# PS.net
KiCad netlist of a schematic drawn in Altium Designer
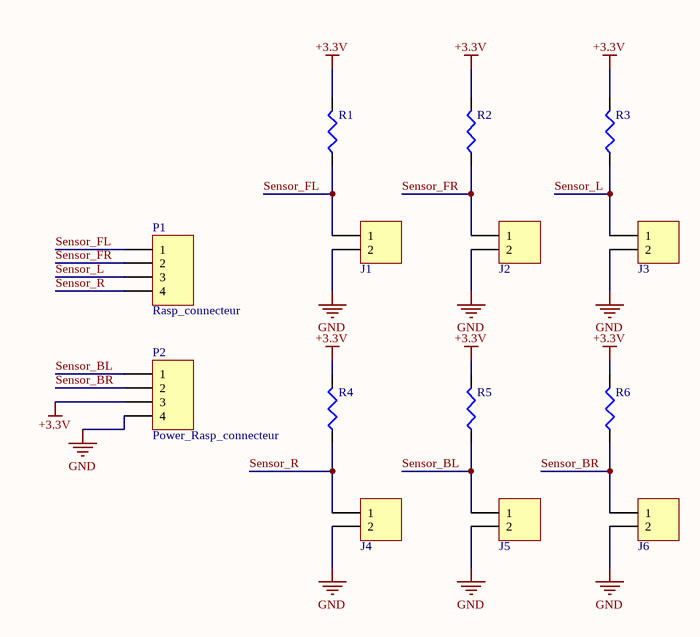
[diagram p0: PS.SchDoc]

(export (version "E")
  (design (tool "Eeschema 10.0.6"))
  (components
    (comp (ref "J1")
      (value "Connecteur 2")
      (footprint "Header_2Ecam")
      (description "Connecteur")
      (fields (field (name "DESIGNER") "ECAM 2005"))
      (libsource (lib "HBLib") (part "Connecteur 2"))
    )
    (comp (ref "J2")
      (value "Connecteur 2")
      (footprint "Header_2Ecam")
      (description "Connecteur")
      (fields (field (name "DESIGNER") "ECAM 2005"))
      (libsource (lib "HBLib") (part "Connecteur 2"))
    )
    (comp (ref "J3")
      (value "Connecteur 2")
      (footprint "Header_2Ecam")
      (description "Connecteur")
      (fields (field (name "DESIGNER") "ECAM 2005"))
      (libsource (lib "HBLib") (part "Connecteur 2"))
    )
    (comp (ref "J4")
      (value "Connecteur 2")
      (footprint "Header_2Ecam")
      (description "Connecteur")
      (fields (field (name "DESIGNER") "ECAM 2005"))
      (libsource (lib "HBLib") (part "Connecteur 2"))
    )
    (comp (ref "J5")
      (value "Connecteur 2")
      (footprint "Header_2Ecam")
      (description "Connecteur")
      (fields (field (name "DESIGNER") "ECAM 2005"))
      (libsource (lib "HBLib") (part "Connecteur 2"))
    )
    (comp (ref "J6")
      (value "Connecteur 2")
      (footprint "Header_2Ecam")
      (description "Connecteur")
      (fields (field (name "DESIGNER") "ECAM 2005"))
      (libsource (lib "HBLib") (part "Connecteur 2"))
    )
    (comp (ref "P1")
      (value "Rasp_connecteur")
      (footprint "Header4_ecam")
      (description "Header, 4-Pin")
      (fields (field (name "PUBLISHER") "Altium Limited"))
      (libsource (lib "HBLib") (part "Header 4"))
    )
    (comp (ref "P2")
      (value "Power_Rasp_connecteur")
      (footprint "Header4_ecam")
      (description "Header, 4-Pin")
      (fields (field (name "PUBLISHER") "Altium Limited"))
      (libsource (lib "HBLib") (part "Header 4"))
    )
    (comp (ref "R1")
      (value "Résistance")
      (footprint "AXIAL-0.3")
      (description "Résistance standard")
      (fields (field (name "DESIGNER") "ECAM 2005"))
      (libsource (lib "ECAM") (part "Résistance"))
    )
    (comp (ref "R2")
      (value "Résistance")
      (footprint "AXIAL-0.3")
      (description "Résistance standard")
      (fields (field (name "DESIGNER") "ECAM 2005"))
      (libsource (lib "ECAM") (part "Résistance"))
    )
    (comp (ref "R3")
      (value "Résistance")
      (footprint "AXIAL-0.3")
      (description "Résistance standard")
      (fields (field (name "DESIGNER") "ECAM 2005"))
      (libsource (lib "ECAM") (part "Résistance"))
    )
    (comp (ref "R4")
      (value "Résistance")
      (footprint "AXIAL-0.3")
      (description "Résistance standard")
      (fields (field (name "DESIGNER") "ECAM 2005"))
      (libsource (lib "ECAM") (part "Résistance"))
    )
    (comp (ref "R5")
      (value "Résistance")
      (footprint "AXIAL-0.3")
      (description "Résistance standard")
      (fields (field (name "DESIGNER") "ECAM 2005"))
      (libsource (lib "ECAM") (part "Résistance"))
    )
    (comp (ref "R6")
      (value "Résistance")
      (footprint "AXIAL-0.3")
      (description "Résistance standard")
      (fields (field (name "DESIGNER") "ECAM 2005"))
      (libsource (lib "ECAM") (part "Résistance"))
    )
  )
  (nets
    (net (code "1") (name "+3.3V") (class "Default")
      (node (ref "P2") (pin "3") (pinfunction "3_3") (pintype "passive"))
      (node (ref "R1") (pin "2") (pinfunction "2_2") (pintype "passive"))
      (node (ref "R2") (pin "2") (pinfunction "2_2") (pintype "passive"))
      (node (ref "R3") (pin "2") (pinfunction "2_2") (pintype "passive"))
      (node (ref "R4") (pin "2") (pinfunction "2_2") (pintype "passive"))
      (node (ref "R5") (pin "2") (pinfunction "2_2") (pintype "passive"))
      (node (ref "R6") (pin "2") (pinfunction "2_2") (pintype "passive"))
    )
    (net (code "2") (name "/Sensor_BL") (class "Default")
      (node (ref "J5") (pin "1") (pinfunction "1_1") (pintype "passive"))
      (node (ref "P2") (pin "1") (pinfunction "1_1") (pintype "passive"))
      (node (ref "R5") (pin "1") (pinfunction "1_1") (pintype "passive"))
    )
    (net (code "3") (name "/Sensor_BR") (class "Default")
      (node (ref "J6") (pin "1") (pinfunction "1_1") (pintype "passive"))
      (node (ref "P2") (pin "2") (pinfunction "2_2") (pintype "passive"))
      (node (ref "R6") (pin "1") (pinfunction "1_1") (pintype "passive"))
    )
    (net (code "4") (name "/Sensor_FL") (class "Default")
      (node (ref "J1") (pin "1") (pinfunction "1_1") (pintype "passive"))
      (node (ref "P1") (pin "1") (pinfunction "1_1") (pintype "passive"))
      (node (ref "R1") (pin "1") (pinfunction "1_1") (pintype "passive"))
    )
    (net (code "5") (name "/Sensor_FR") (class "Default")
      (node (ref "J2") (pin "1") (pinfunction "1_1") (pintype "passive"))
      (node (ref "P1") (pin "2") (pinfunction "2_2") (pintype "passive"))
      (node (ref "R2") (pin "1") (pinfunction "1_1") (pintype "passive"))
    )
    (net (code "6") (name "/Sensor_L") (class "Default")
      (node (ref "J3") (pin "1") (pinfunction "1_1") (pintype "passive"))
      (node (ref "P1") (pin "3") (pinfunction "3_3") (pintype "passive"))
      (node (ref "R3") (pin "1") (pinfunction "1_1") (pintype "passive"))
    )
    (net (code "7") (name "/Sensor_R") (class "Default")
      (node (ref "J4") (pin "1") (pinfunction "1_1") (pintype "passive"))
      (node (ref "P1") (pin "4") (pinfunction "4_4") (pintype "passive"))
      (node (ref "R4") (pin "1") (pinfunction "1_1") (pintype "passive"))
    )
    (net (code "8") (name "GND") (class "Default")
      (node (ref "J1") (pin "2") (pinfunction "2_2") (pintype "passive"))
      (node (ref "J2") (pin "2") (pinfunction "2_2") (pintype "passive"))
      (node (ref "J3") (pin "2") (pinfunction "2_2") (pintype "passive"))
      (node (ref "J4") (pin "2") (pinfunction "2_2") (pintype "passive"))
      (node (ref "J5") (pin "2") (pinfunction "2_2") (pintype "passive"))
      (node (ref "J6") (pin "2") (pinfunction "2_2") (pintype "passive"))
      (node (ref "P2") (pin "4") (pinfunction "4_4") (pintype "passive"))
    )
  )
)
